# design.net
KiCad netlist of a schematic drawn in EasyEDA Pro
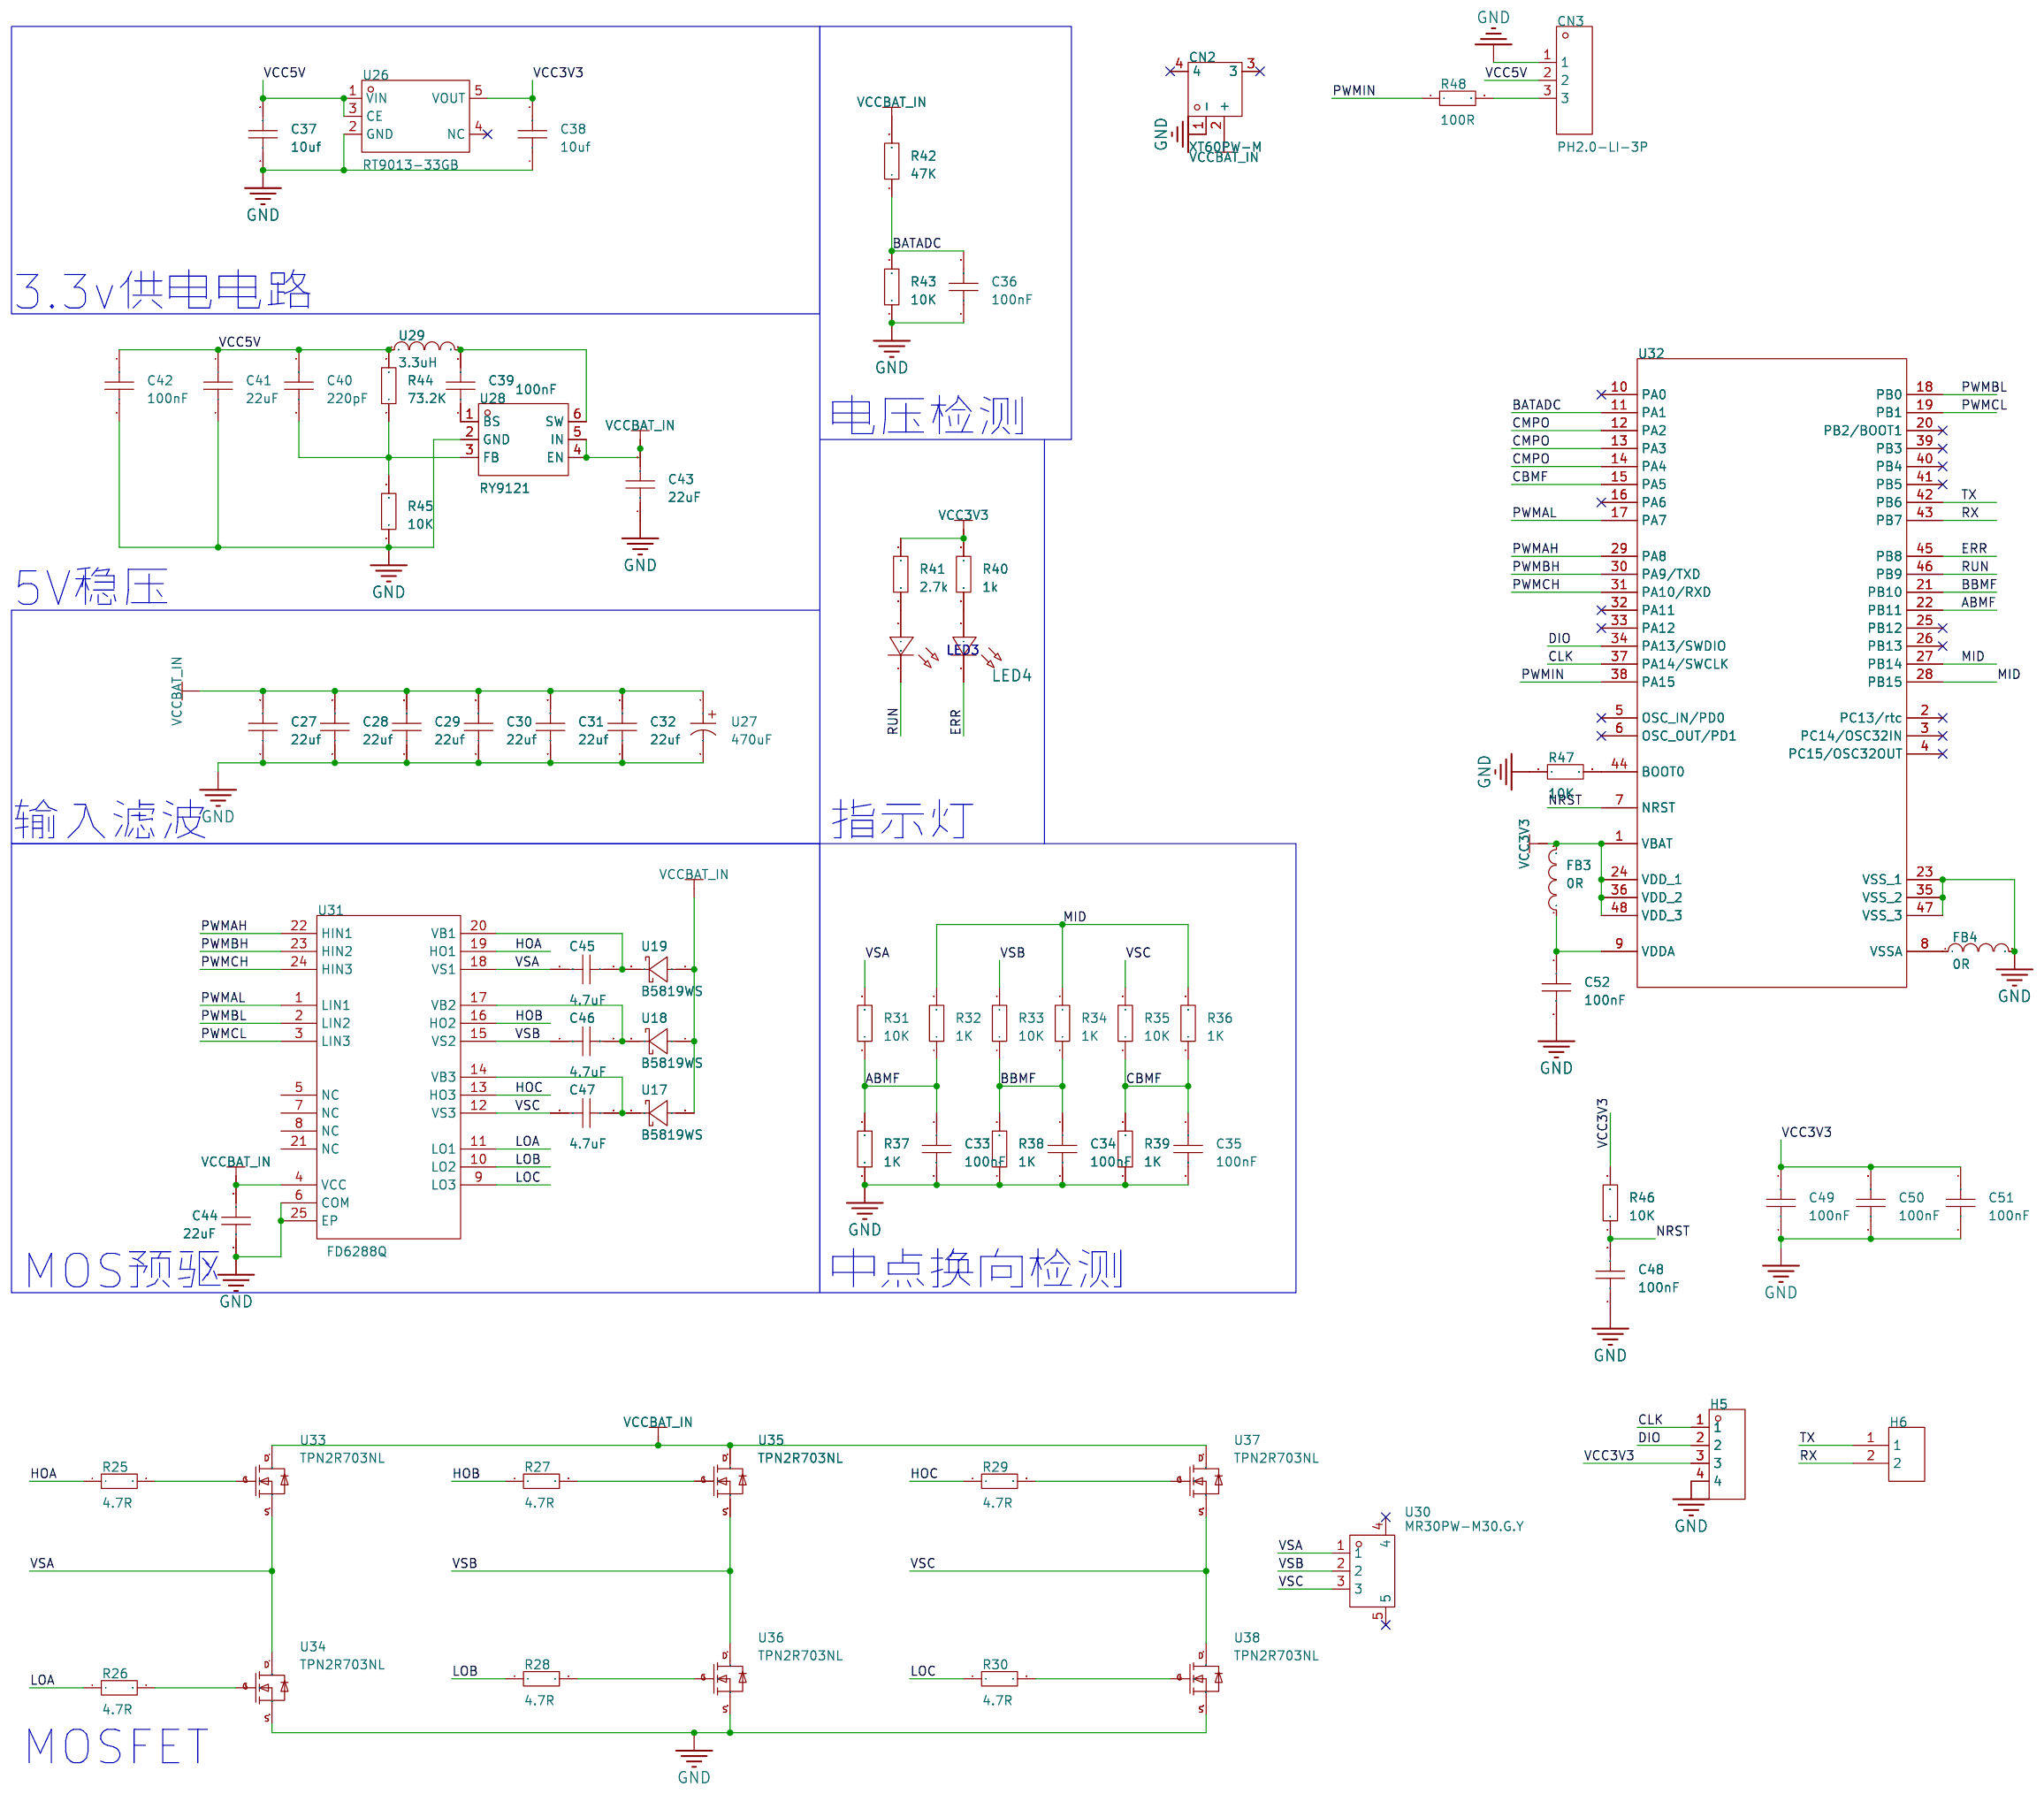
[diagram p0: schematic sheet]

(export (version "E")
  (design (tool "Eeschema 10.0.6"))
  (components
    (comp (ref "C27")
      (value "22uf")
      (footprint "easyedapro:C0603")
      (libsource (lib "easyedapro") (part "CapAcitance"))
    )
    (comp (ref "C28")
      (value "22uf")
      (footprint "easyedapro:C0603")
      (libsource (lib "easyedapro") (part "CapAcitance"))
    )
    (comp (ref "C29")
      (value "22uf")
      (footprint "easyedapro:C0603")
      (libsource (lib "easyedapro") (part "CapAcitance"))
    )
    (comp (ref "C30")
      (value "22uf")
      (footprint "easyedapro:C0603")
      (libsource (lib "easyedapro") (part "CapAcitance"))
    )
    (comp (ref "C31")
      (value "22uf")
      (footprint "easyedapro:C0603")
      (libsource (lib "easyedapro") (part "CapAcitance"))
    )
    (comp (ref "C32")
      (value "22uf")
      (footprint "easyedapro:C0603")
      (libsource (lib "easyedapro") (part "CapAcitance"))
    )
    (comp (ref "C33")
      (value "100nF")
      (footprint "easyedapro:C0603")
      (libsource (lib "easyedapro") (part "CapAcitance"))
    )
    (comp (ref "C34")
      (value "100nF")
      (footprint "easyedapro:C0603")
      (libsource (lib "easyedapro") (part "CapAcitance"))
    )
    (comp (ref "C35")
      (value "100nF")
      (footprint "easyedapro:C0603")
      (libsource (lib "easyedapro") (part "CapAcitance"))
    )
    (comp (ref "C36")
      (value "100nF")
      (footprint "easyedapro:C0603")
      (libsource (lib "easyedapro") (part "CapAcitance"))
    )
    (comp (ref "C37")
      (value "10uf")
      (footprint "easyedapro:C0603")
      (libsource (lib "easyedapro") (part "CapAcitance"))
    )
    (comp (ref "C38")
      (value "10uf")
      (footprint "easyedapro:C0603")
      (libsource (lib "easyedapro") (part "CapAcitance"))
    )
    (comp (ref "C39")
      (value "100nF")
      (footprint "easyedapro:C0603")
      (libsource (lib "easyedapro") (part "CapAcitance"))
    )
    (comp (ref "C40")
      (value "220pF")
      (footprint "easyedapro:C0603")
      (libsource (lib "easyedapro") (part "CapAcitance"))
    )
    (comp (ref "C41")
      (value "22uF")
      (footprint "easyedapro:C0603")
      (libsource (lib "easyedapro") (part "CapAcitance"))
    )
    (comp (ref "C42")
      (value "100nF")
      (footprint "easyedapro:C0603")
      (libsource (lib "easyedapro") (part "CapAcitance"))
    )
    (comp (ref "C43")
      (value "22uF")
      (footprint "easyedapro:C0603")
      (libsource (lib "easyedapro") (part "CapAcitance"))
    )
    (comp (ref "C44")
      (value "22uF")
      (footprint "easyedapro:C0603")
      (libsource (lib "easyedapro") (part "CapAcitance"))
    )
    (comp (ref "C45")
      (value "4.7uF")
      (footprint "easyedapro:C0603")
      (libsource (lib "easyedapro") (part "CapAcitance"))
    )
    (comp (ref "C46")
      (value "4.7uF")
      (footprint "easyedapro:C0603")
      (libsource (lib "easyedapro") (part "CapAcitance"))
    )
    (comp (ref "C47")
      (value "4.7uF")
      (footprint "easyedapro:C0603")
      (libsource (lib "easyedapro") (part "CapAcitance"))
    )
    (comp (ref "C48")
      (value "100nF")
      (footprint "easyedapro:C0603")
      (libsource (lib "easyedapro") (part "CapAcitance"))
    )
    (comp (ref "C49")
      (value "100nF")
      (footprint "easyedapro:C0603")
      (libsource (lib "easyedapro") (part "CapAcitance"))
    )
    (comp (ref "C50")
      (value "100nF")
      (footprint "easyedapro:C0603")
      (libsource (lib "easyedapro") (part "CapAcitance"))
    )
    (comp (ref "C51")
      (value "100nF")
      (footprint "easyedapro:C0603")
      (libsource (lib "easyedapro") (part "CapAcitance"))
    )
    (comp (ref "C52")
      (value "100nF")
      (footprint "easyedapro:C0603")
      (libsource (lib "easyedapro") (part "CapAcitance"))
    )
    (comp (ref "CN2")
      (value "XT60PW-M")
      (footprint "easyedapro:CONN-TH_XT60PW-M")
      (description "模型锂电连接器")
      (fields (field (name "Manufacturer") "AMASS(艾迈斯)"))
      (libsource (lib "easyedapro") (part "XT60PW-M"))
    )
    (comp (ref "CN3")
      (value "PH2.0-LI-3P")
      (footprint "easyedapro:CONN-TH_3P-P2.00_HX20007-3A")
      (libsource (lib "easyedapro") (part "PH2.0-LI-3P"))
    )
    (comp (ref "FB3")
      (value "0R")
      (footprint "easyedapro:L0603")
      (libsource (lib "easyedapro") (part "SDFL1608S100KTF"))
    )
    (comp (ref "FB4")
      (value "0R")
      (footprint "easyedapro:L0603")
      (libsource (lib "easyedapro") (part "SDFL1608S100KTF"))
    )
    (comp (ref "H5") (value "~") (libsource (lib "easyedapro") (part "2.54-1*4p母")))
    (comp (ref "H6")
      (value "~")
      (footprint "easyedapro:HalfHole-2.0-1*2P")
      (libsource (lib "easyedapro") (part "HDR2.0-1*2"))
    )
    (comp (ref "LED3") (value "~") (libsource (lib "easyedapro") (part "led_g")))
    (comp (ref "LED4") (value "~") (libsource (lib "easyedapro") (part "led_r")))
    (comp (ref "R25")
      (value "4.7R")
      (footprint "easyedapro:R0603")
      (libsource (lib "easyedapro") (part "电阻"))
    )
    (comp (ref "R26")
      (value "4.7R")
      (footprint "easyedapro:R0603")
      (libsource (lib "easyedapro") (part "电阻"))
    )
    (comp (ref "R27")
      (value "4.7R")
      (footprint "easyedapro:R0603")
      (libsource (lib "easyedapro") (part "电阻"))
    )
    (comp (ref "R28")
      (value "4.7R")
      (footprint "easyedapro:R0603")
      (libsource (lib "easyedapro") (part "电阻"))
    )
    (comp (ref "R29")
      (value "4.7R")
      (footprint "easyedapro:R0603")
      (libsource (lib "easyedapro") (part "电阻"))
    )
    (comp (ref "R30")
      (value "4.7R")
      (footprint "easyedapro:R0603")
      (libsource (lib "easyedapro") (part "电阻"))
    )
    (comp (ref "R31") (value "10K") (footprint "easyedapro:R0603") (libsource (lib "easyedapro") (part "电阻")))
    (comp (ref "R32") (value "1K") (footprint "easyedapro:R0603") (libsource (lib "easyedapro") (part "电阻")))
    (comp (ref "R33") (value "10K") (footprint "easyedapro:R0603") (libsource (lib "easyedapro") (part "电阻")))
    (comp (ref "R34") (value "1K") (footprint "easyedapro:R0603") (libsource (lib "easyedapro") (part "电阻")))
    (comp (ref "R35") (value "10K") (footprint "easyedapro:R0603") (libsource (lib "easyedapro") (part "电阻")))
    (comp (ref "R36") (value "1K") (footprint "easyedapro:R0603") (libsource (lib "easyedapro") (part "电阻")))
    (comp (ref "R37") (value "1K") (footprint "easyedapro:R0603") (libsource (lib "easyedapro") (part "电阻")))
    (comp (ref "R38") (value "1K") (footprint "easyedapro:R0603") (libsource (lib "easyedapro") (part "电阻")))
    (comp (ref "R39") (value "1K") (footprint "easyedapro:R0603") (libsource (lib "easyedapro") (part "电阻")))
    (comp (ref "R40") (value "1k") (footprint "easyedapro:R0603") (libsource (lib "easyedapro") (part "电阻")))
    (comp (ref "R41")
      (value "2.7k")
      (footprint "easyedapro:R0603")
      (libsource (lib "easyedapro") (part "电阻"))
    )
    (comp (ref "R42") (value "47K") (footprint "easyedapro:R0603") (libsource (lib "easyedapro") (part "电阻")))
    (comp (ref "R43") (value "10K") (footprint "easyedapro:R0603") (libsource (lib "easyedapro") (part "电阻")))
    (comp (ref "R44")
      (value "73.2K")
      (footprint "easyedapro:R0603")
      (libsource (lib "easyedapro") (part "电阻"))
    )
    (comp (ref "R45") (value "10K") (footprint "easyedapro:R0603") (libsource (lib "easyedapro") (part "电阻")))
    (comp (ref "R46") (value "10K") (footprint "easyedapro:R0603") (libsource (lib "easyedapro") (part "电阻")))
    (comp (ref "R47") (value "10K") (footprint "easyedapro:R0603") (libsource (lib "easyedapro") (part "电阻")))
    (comp (ref "R48")
      (value "100R")
      (footprint "easyedapro:R0603")
      (libsource (lib "easyedapro") (part "电阻"))
    )
    (comp (ref "U17")
      (value "B5819WS")
      (footprint "easyedapro:SOD-123_L2.8-W1.8-LS3.7-FD")
      (libsource (lib "easyedapro") (part "B5819WS_C9900015711"))
    )
    (comp (ref "U18")
      (value "B5819WS")
      (footprint "easyedapro:SOD-123_L2.8-W1.8-LS3.7-FD")
      (libsource (lib "easyedapro") (part "B5819WS_C9900015711"))
    )
    (comp (ref "U19")
      (value "B5819WS")
      (footprint "easyedapro:SOD-123_L2.8-W1.8-LS3.7-FD")
      (libsource (lib "easyedapro") (part "B5819WS_C9900015711"))
    )
    (comp (ref "U26")
      (value "RT9013-33GB")
      (footprint "easyedapro:SOT-23-5_L2.9-W1.6-P0.95-LS2.8-BR")
      (fields (field (name "Manufacturer") "TECH PUBLIC(台舟)"))
      (libsource (lib "easyedapro") (part "RT9013-33GB_C19268157"))
    )
    (comp (ref "U27")
      (value "470uF")
      (footprint "easyedapro:CAP-SMD_BD8.0-L8.3-W8.3-LS9.1-FD")
      (description "容值:470uF;精度:±20%;额定电压:16V;纹波电流:390mA@120Hz;等效串联电阻:-;")
      (fields (field (name "Manufacturer Part") "865060353009") (field (name "Manufacturer") "Wurth(伍尔特)"))
      (libsource (lib "easyedapro") (part "865060353009"))
    )
    (comp (ref "U28")
      (value "RY9121")
      (footprint "easyedapro:SOT-23-6_L2.9-W1.6-P0.95-LS2.8-BR")
      (description "功能类型:降压型;输入电压:4.5V~17V;输出电流(最大值):2A;")
      (fields (field (name "Manufacturer") "RYCHiP(蕊源)"))
      (libsource (lib "easyedapro") (part "RY9121"))
    )
    (comp (ref "U29")
      (value "3.3uH")
      (footprint "easyedapro:IND-SMD_L12.3-W12.3_SMDRI127")
      (fields (field (name "Manufacturer Part") "CDRH127R"))
      (libsource (lib "easyedapro") (part "CDRH127R"))
    )
    (comp (ref "U30")
      (value "MR30PW-M30.G.Y")
      (footprint "easyedapro:CONN-TH_MR30PW-M30-G-Y")
      (fields (field (name "Manufacturer") "AMASS(艾迈斯)"))
      (libsource (lib "easyedapro") (part "MR30PW-M30.G.Y"))
    )
    (comp (ref "U31")
      (value "FD6288Q")
      (footprint "easyedapro:QFN-24")
      (libsource (lib "easyedapro") (part "FD6288Q"))
    )
    (comp (ref "U32")
      (value "~")
      (footprint "easyedapro:LQFP-48_L7.0-W7.0-P0.50-LS9.0-BL")
      (libsource (lib "easyedapro") (part "CH32V203C8T6"))
    )
    (comp (ref "U33")
      (value "TPN2R703NL")
      (footprint "easyedapro:TPN2R703NL")
      (libsource (lib "easyedapro") (part "TPN2R703NL"))
    )
    (comp (ref "U34")
      (value "TPN2R703NL")
      (footprint "easyedapro:TPN2R703NL")
      (libsource (lib "easyedapro") (part "TPN2R703NL"))
    )
    (comp (ref "U35")
      (value "TPN2R703NL")
      (footprint "easyedapro:TPN2R703NL")
      (libsource (lib "easyedapro") (part "TPN2R703NL"))
    )
    (comp (ref "U36")
      (value "TPN2R703NL")
      (footprint "easyedapro:TPN2R703NL")
      (libsource (lib "easyedapro") (part "TPN2R703NL"))
    )
    (comp (ref "U37")
      (value "TPN2R703NL")
      (footprint "easyedapro:TPN2R703NL")
      (libsource (lib "easyedapro") (part "TPN2R703NL"))
    )
    (comp (ref "U38")
      (value "TPN2R703NL")
      (footprint "easyedapro:TPN2R703NL")
      (libsource (lib "easyedapro") (part "TPN2R703NL"))
    )
  )
  (nets
    (net (code "1") (name "/ABMF") (class "Default")
      (node (ref "C33") (pin "1") (pinfunction "1_1") (pintype "input"))
      (node (ref "R31") (pin "1") (pinfunction "1_1") (pintype "input"))
      (node (ref "R32") (pin "1") (pinfunction "1_1") (pintype "input"))
      (node (ref "R37") (pin "2") (pinfunction "2_2") (pintype "input"))
      (node (ref "U32") (pin "22") (pinfunction "PB11_22") (pintype "input"))
    )
    (net (code "2") (name "/BATADC") (class "Default")
      (node (ref "C36") (pin "2") (pinfunction "2_2") (pintype "input"))
      (node (ref "R42") (pin "1") (pinfunction "1_1") (pintype "input"))
      (node (ref "R43") (pin "2") (pinfunction "2_2") (pintype "input"))
      (node (ref "U32") (pin "11") (pinfunction "PA1_11") (pintype "input"))
    )
    (net (code "3") (name "/BBMF") (class "Default")
      (node (ref "C34") (pin "1") (pinfunction "1_1") (pintype "input"))
      (node (ref "R33") (pin "1") (pinfunction "1_1") (pintype "input"))
      (node (ref "R34") (pin "1") (pinfunction "1_1") (pintype "input"))
      (node (ref "R38") (pin "2") (pinfunction "2_2") (pintype "input"))
      (node (ref "U32") (pin "21") (pinfunction "PB10_21") (pintype "input"))
    )
    (net (code "4") (name "/CBMF") (class "Default")
      (node (ref "C35") (pin "1") (pinfunction "1_1") (pintype "input"))
      (node (ref "R35") (pin "1") (pinfunction "1_1") (pintype "input"))
      (node (ref "R36") (pin "1") (pinfunction "1_1") (pintype "input"))
      (node (ref "R39") (pin "2") (pinfunction "2_2") (pintype "input"))
      (node (ref "U32") (pin "15") (pinfunction "PA5_15") (pintype "input"))
    )
    (net (code "5") (name "/CLK") (class "Default")
      (node (ref "H5") (pin "1") (pinfunction "1_1") (pintype "input"))
      (node (ref "U32") (pin "37") (pinfunction "PA14/SWCLK_37") (pintype "input"))
    )
    (net (code "6") (name "/CMPO") (class "Default")
      (node (ref "U32") (pin "12") (pinfunction "PA2_12") (pintype "input"))
      (node (ref "U32") (pin "13") (pinfunction "PA3_13") (pintype "input"))
      (node (ref "U32") (pin "14") (pinfunction "PA4_14") (pintype "input"))
    )
    (net (code "7") (name "/DIO") (class "Default")
      (node (ref "H5") (pin "2") (pinfunction "2_2") (pintype "input"))
      (node (ref "U32") (pin "34") (pinfunction "PA13/SWDIO_34") (pintype "input"))
    )
    (net (code "8") (name "/ERR") (class "Default")
      (node (ref "LED4") (pin "1") (pinfunction "C_1") (pintype "input"))
      (node (ref "U32") (pin "45") (pinfunction "PB8_45") (pintype "input"))
    )
    (net (code "9") (name "/HOA") (class "Default")
      (node (ref "R25") (pin "1") (pinfunction "1_1") (pintype "input"))
      (node (ref "U31") (pin "19") (pinfunction "HO1_19") (pintype "output"))
    )
    (net (code "10") (name "/HOB") (class "Default")
      (node (ref "R27") (pin "1") (pinfunction "1_1") (pintype "input"))
      (node (ref "U31") (pin "16") (pinfunction "HO2_16") (pintype "output"))
    )
    (net (code "11") (name "/HOC") (class "Default")
      (node (ref "R29") (pin "1") (pinfunction "1_1") (pintype "input"))
      (node (ref "U31") (pin "13") (pinfunction "HO3_13") (pintype "output"))
    )
    (net (code "12") (name "/LOA") (class "Default")
      (node (ref "R26") (pin "1") (pinfunction "1_1") (pintype "input"))
      (node (ref "U31") (pin "11") (pinfunction "LO1_11") (pintype "output"))
    )
    (net (code "13") (name "/LOB") (class "Default")
      (node (ref "R28") (pin "1") (pinfunction "1_1") (pintype "input"))
      (node (ref "U31") (pin "10") (pinfunction "LO2_10") (pintype "output"))
    )
    (net (code "14") (name "/LOC") (class "Default")
      (node (ref "R30") (pin "1") (pinfunction "1_1") (pintype "input"))
      (node (ref "U31") (pin "9") (pinfunction "LO3_9") (pintype "output"))
    )
    (net (code "15") (name "/MID") (class "Default")
      (node (ref "R32") (pin "2") (pinfunction "2_2") (pintype "input"))
      (node (ref "R34") (pin "2") (pinfunction "2_2") (pintype "input"))
      (node (ref "R36") (pin "2") (pinfunction "2_2") (pintype "input"))
      (node (ref "U32") (pin "27") (pinfunction "PB14_27") (pintype "input"))
      (node (ref "U32") (pin "28") (pinfunction "PB15_28") (pintype "input"))
    )
    (net (code "16") (name "/NRST") (class "Default")
      (node (ref "C48") (pin "2") (pinfunction "2_2") (pintype "input"))
      (node (ref "R46") (pin "1") (pinfunction "1_1") (pintype "input"))
      (node (ref "U32") (pin "7") (pinfunction "NRST_7") (pintype "input"))
    )
    (net (code "17") (name "/PWMAH") (class "Default")
      (node (ref "U31") (pin "22") (pinfunction "HIN1_22") (pintype "input"))
      (node (ref "U32") (pin "29") (pinfunction "PA8_29") (pintype "input"))
    )
    (net (code "18") (name "/PWMAL") (class "Default")
      (node (ref "U31") (pin "1") (pinfunction "LIN1_1") (pintype "input"))
      (node (ref "U32") (pin "17") (pinfunction "PA7_17") (pintype "input"))
    )
    (net (code "19") (name "/PWMBH") (class "Default")
      (node (ref "U31") (pin "23") (pinfunction "HIN2_23") (pintype "input"))
      (node (ref "U32") (pin "30") (pinfunction "PA9/TXD_30") (pintype "input"))
    )
    (net (code "20") (name "/PWMBL") (class "Default")
      (node (ref "U31") (pin "2") (pinfunction "LIN2_2") (pintype "input"))
      (node (ref "U32") (pin "18") (pinfunction "PB0_18") (pintype "input"))
    )
    (net (code "21") (name "/PWMCH") (class "Default")
      (node (ref "U31") (pin "24") (pinfunction "HIN3_24") (pintype "input"))
      (node (ref "U32") (pin "31") (pinfunction "PA10/RXD_31") (pintype "input"))
    )
    (net (code "22") (name "/PWMCL") (class "Default")
      (node (ref "U31") (pin "3") (pinfunction "LIN3_3") (pintype "input"))
      (node (ref "U32") (pin "19") (pinfunction "PB1_19") (pintype "input"))
    )
    (net (code "23") (name "/PWMIN") (class "Default")
      (node (ref "R48") (pin "1") (pinfunction "1_1") (pintype "input"))
      (node (ref "U32") (pin "38") (pinfunction "PA15_38") (pintype "input"))
    )
    (net (code "24") (name "/RUN") (class "Default")
      (node (ref "LED3") (pin "1") (pinfunction "C_1") (pintype "input"))
      (node (ref "U32") (pin "46") (pinfunction "PB9_46") (pintype "input"))
    )
    (net (code "25") (name "/RX") (class "Default")
      (node (ref "H6") (pin "2") (pinfunction "2_2") (pintype "input"))
      (node (ref "U32") (pin "43") (pinfunction "PB7_43") (pintype "input"))
    )
    (net (code "26") (name "/TX") (class "Default")
      (node (ref "H6") (pin "1") (pinfunction "1_1") (pintype "input"))
      (node (ref "U32") (pin "42") (pinfunction "PB6_42") (pintype "input"))
    )
    (net (code "27") (name "/VCC5V") (class "Default")
      (node (ref "C37") (pin "2") (pinfunction "2_2") (pintype "input"))
      (node (ref "C40") (pin "1") (pinfunction "1_1") (pintype "input"))
      (node (ref "C41") (pin "1") (pinfunction "1_1") (pintype "input"))
      (node (ref "C42") (pin "1") (pinfunction "1_1") (pintype "input"))
      (node (ref "CN3") (pin "2") (pinfunction "2_2") (pintype "input"))
      (node (ref "R44") (pin "2") (pinfunction "2_2") (pintype "input"))
      (node (ref "U26") (pin "1") (pinfunction "VIN_1") (pintype "unspecified"))
      (node (ref "U26") (pin "3") (pinfunction "CE_3") (pintype "unspecified"))
      (node (ref "U29") (pin "1") (pinfunction "1_1") (pintype "input"))
    )
    (net (code "28") (name "/VSA") (class "Default")
      (node (ref "C45") (pin "1") (pinfunction "1_1") (pintype "input"))
      (node (ref "R31") (pin "2") (pinfunction "2_2") (pintype "input"))
      (node (ref "U30") (pin "1") (pinfunction "1_1") (pintype "unspecified"))
      (node (ref "U31") (pin "18") (pinfunction "VS1_18") (pintype "input"))
      (node (ref "U33") (pin "3") (pinfunction "S_3") (pintype "unspecified"))
      (node (ref "U34") (pin "1") (pinfunction "D_1") (pintype "unspecified"))
    )
    (net (code "29") (name "/VSB") (class "Default")
      (node (ref "C46") (pin "1") (pinfunction "1_1") (pintype "input"))
      (node (ref "R33") (pin "2") (pinfunction "2_2") (pintype "input"))
      (node (ref "U30") (pin "2") (pinfunction "2_2") (pintype "unspecified"))
      (node (ref "U31") (pin "15") (pinfunction "VS2_15") (pintype "input"))
      (node (ref "U35") (pin "3") (pinfunction "S_3") (pintype "unspecified"))
      (node (ref "U36") (pin "1") (pinfunction "D_1") (pintype "unspecified"))
    )
    (net (code "30") (name "/VSC") (class "Default")
      (node (ref "C47") (pin "1") (pinfunction "1_1") (pintype "input"))
      (node (ref "R35") (pin "2") (pinfunction "2_2") (pintype "input"))
      (node (ref "U30") (pin "3") (pinfunction "3_3") (pintype "unspecified"))
      (node (ref "U31") (pin "12") (pinfunction "VS3_12") (pintype "input"))
      (node (ref "U37") (pin "3") (pinfunction "S_3") (pintype "unspecified"))
      (node (ref "U38") (pin "1") (pinfunction "D_1") (pintype "unspecified"))
    )
    (net (code "31") (name "GND") (class "Default")
      (node (ref "C27") (pin "1") (pinfunction "1_1") (pintype "input"))
      (node (ref "C28") (pin "1") (pinfunction "1_1") (pintype "input"))
      (node (ref "C29") (pin "1") (pinfunction "1_1") (pintype "input"))
      (node (ref "C30") (pin "1") (pinfunction "1_1") (pintype "input"))
      (node (ref "C31") (pin "1") (pinfunction "1_1") (pintype "input"))
      (node (ref "C32") (pin "1") (pinfunction "1_1") (pintype "input"))
      (node (ref "C33") (pin "2") (pinfunction "2_2") (pintype "input"))
      (node (ref "C34") (pin "2") (pinfunction "2_2") (pintype "input"))
      (node (ref "C35") (pin "2") (pinfunction "2_2") (pintype "input"))
      (node (ref "C36") (pin "1") (pinfunction "1_1") (pintype "input"))
      (node (ref "C37") (pin "1") (pinfunction "1_1") (pintype "input"))
      (node (ref "C38") (pin "1") (pinfunction "1_1") (pintype "input"))
      (node (ref "C41") (pin "2") (pinfunction "2_2") (pintype "input"))
      (node (ref "C42") (pin "2") (pinfunction "2_2") (pintype "input"))
      (node (ref "C43") (pin "1") (pinfunction "1_1") (pintype "input"))
      (node (ref "C44") (pin "1") (pinfunction "1_1") (pintype "input"))
      (node (ref "C48") (pin "1") (pinfunction "1_1") (pintype "input"))
      (node (ref "C49") (pin "1") (pinfunction "1_1") (pintype "input"))
      (node (ref "C50") (pin "1") (pinfunction "1_1") (pintype "input"))
      (node (ref "C51") (pin "1") (pinfunction "1_1") (pintype "input"))
      (node (ref "C52") (pin "2") (pinfunction "2_2") (pintype "input"))
      (node (ref "CN2") (pin "1") (pinfunction "-_1") (pintype "input"))
      (node (ref "CN3") (pin "1") (pinfunction "1_1") (pintype "input"))
      (node (ref "FB4") (pin "2") (pinfunction "2_2") (pintype "unspecified"))
      (node (ref "H5") (pin "4") (pinfunction "4_4") (pintype "input"))
      (node (ref "R37") (pin "1") (pinfunction "1_1") (pintype "input"))
      (node (ref "R38") (pin "1") (pinfunction "1_1") (pintype "input"))
      (node (ref "R39") (pin "1") (pinfunction "1_1") (pintype "input"))
      (node (ref "R43") (pin "1") (pinfunction "1_1") (pintype "input"))
      (node (ref "R45") (pin "1") (pinfunction "1_1") (pintype "input"))
      (node (ref "R47") (pin "1") (pinfunction "1_1") (pintype "input"))
      (node (ref "U26") (pin "2") (pinfunction "GND_2") (pintype "unspecified"))
      (node (ref "U27") (pin "2") (pinfunction "2_2") (pintype "input"))
      (node (ref "U28") (pin "2") (pinfunction "GND_2") (pintype "input"))
      (node (ref "U31") (pin "25") (pinfunction "EP_25") (pintype "input"))
      (node (ref "U31") (pin "6") (pinfunction "COM_6") (pintype "input"))
      (node (ref "U32") (pin "23") (pinfunction "VSS_1_23") (pintype "input"))
      (node (ref "U32") (pin "35") (pinfunction "VSS_2_35") (pintype "input"))
      (node (ref "U32") (pin "47") (pinfunction "VSS_3_47") (pintype "input"))
      (node (ref "U34") (pin "3") (pinfunction "S_3") (pintype "unspecified"))
      (node (ref "U36") (pin "3") (pinfunction "S_3") (pintype "unspecified"))
      (node (ref "U38") (pin "3") (pinfunction "S_3") (pintype "unspecified"))
    )
    (net (code "32") (name "Net-(CN3-Pad3)") (class "Default")
      (node (ref "CN3") (pin "3") (pinfunction "3_3") (pintype "input"))
      (node (ref "R48") (pin "2") (pinfunction "2_2") (pintype "input"))
    )
    (net (code "33") (name "Net-(LED3-A)") (class "Default")
      (node (ref "LED3") (pin "2") (pinfunction "A_2") (pintype "input"))
      (node (ref "R41") (pin "2") (pinfunction "2_2") (pintype "input"))
    )
    (net (code "34") (name "Net-(LED4-A)") (class "Default")
      (node (ref "LED4") (pin "2") (pinfunction "A_2") (pintype "input"))
      (node (ref "R40") (pin "2") (pinfunction "2_2") (pintype "input"))
    )
    (net (code "35") (name "Net-(U17-K)") (class "Default")
      (node (ref "C47") (pin "2") (pinfunction "2_2") (pintype "input"))
      (node (ref "U17") (pin "2") (pinfunction "K_2") (pintype "input"))
      (node (ref "U31") (pin "14") (pinfunction "VB3_14") (pintype "input"))
    )
    (net (code "36") (name "Net-(U18-K)") (class "Default")
      (node (ref "C46") (pin "2") (pinfunction "2_2") (pintype "input"))
      (node (ref "U18") (pin "2") (pinfunction "K_2") (pintype "input"))
      (node (ref "U31") (pin "17") (pinfunction "VB2_17") (pintype "input"))
    )
    (net (code "37") (name "Net-(U19-K)") (class "Default")
      (node (ref "C45") (pin "2") (pinfunction "2_2") (pintype "input"))
      (node (ref "U19") (pin "2") (pinfunction "K_2") (pintype "input"))
      (node (ref "U31") (pin "20") (pinfunction "VB1_20") (pintype "input"))
    )
    (net (code "38") (name "Net-(U28-BS)") (class "Default")
      (node (ref "C39") (pin "1") (pinfunction "1_1") (pintype "input"))
      (node (ref "U28") (pin "1") (pinfunction "BS_1") (pintype "input"))
    )
    (net (code "39") (name "Net-(U28-FB)") (class "Default")
      (node (ref "C40") (pin "2") (pinfunction "2_2") (pintype "input"))
      (node (ref "R44") (pin "1") (pinfunction "1_1") (pintype "input"))
      (node (ref "R45") (pin "2") (pinfunction "2_2") (pintype "input"))
      (node (ref "U28") (pin "3") (pinfunction "FB_3") (pintype "input"))
    )
    (net (code "40") (name "Net-(U28-SW)") (class "Default")
      (node (ref "C39") (pin "2") (pinfunction "2_2") (pintype "input"))
      (node (ref "U28") (pin "6") (pinfunction "SW_6") (pintype "input"))
      (node (ref "U29") (pin "2") (pinfunction "2_2") (pintype "input"))
    )
    (net (code "41") (name "Net-(U32-BOOT0)") (class "Default")
      (node (ref "R47") (pin "2") (pinfunction "2_2") (pintype "input"))
      (node (ref "U32") (pin "44") (pinfunction "BOOT0_44") (pintype "input"))
    )
    (net (code "42") (name "Net-(U32-VDDA)") (class "Default")
      (node (ref "C52") (pin "1") (pinfunction "1_1") (pintype "input"))
      (node (ref "FB3") (pin "1") (pinfunction "1_1") (pintype "unspecified"))
      (node (ref "U32") (pin "9") (pinfunction "VDDA_9") (pintype "input"))
    )
    (net (code "43") (name "Net-(U32-VSSA)") (class "Default")
      (node (ref "FB4") (pin "1") (pinfunction "1_1") (pintype "unspecified"))
      (node (ref "U32") (pin "8") (pinfunction "VSSA_8") (pintype "input"))
    )
    (net (code "44") (name "Net-(U33-G)") (class "Default")
      (node (ref "R25") (pin "2") (pinfunction "2_2") (pintype "input"))
      (node (ref "U33") (pin "2") (pinfunction "G_2") (pintype "unspecified"))
    )
    (net (code "45") (name "Net-(U34-G)") (class "Default")
      (node (ref "R26") (pin "2") (pinfunction "2_2") (pintype "input"))
      (node (ref "U34") (pin "2") (pinfunction "G_2") (pintype "unspecified"))
    )
    (net (code "46") (name "Net-(U35-G)") (class "Default")
      (node (ref "R27") (pin "2") (pinfunction "2_2") (pintype "input"))
      (node (ref "U35") (pin "2") (pinfunction "G_2") (pintype "unspecified"))
    )
    (net (code "47") (name "Net-(U36-G)") (class "Default")
      (node (ref "R28") (pin "2") (pinfunction "2_2") (pintype "input"))
      (node (ref "U36") (pin "2") (pinfunction "G_2") (pintype "unspecified"))
    )
    (net (code "48") (name "Net-(U37-G)") (class "Default")
      (node (ref "R29") (pin "2") (pinfunction "2_2") (pintype "input"))
      (node (ref "U37") (pin "2") (pinfunction "G_2") (pintype "unspecified"))
    )
    (net (code "49") (name "Net-(U38-G)") (class "Default")
      (node (ref "R30") (pin "2") (pinfunction "2_2") (pintype "input"))
      (node (ref "U38") (pin "2") (pinfunction "G_2") (pintype "unspecified"))
    )
    (net (code "50") (name "VCC3V3") (class "Default")
      (node (ref "C38") (pin "2") (pinfunction "2_2") (pintype "input"))
      (node (ref "C49") (pin "2") (pinfunction "2_2") (pintype "input"))
      (node (ref "C50") (pin "2") (pinfunction "2_2") (pintype "input"))
      (node (ref "C51") (pin "2") (pinfunction "2_2") (pintype "input"))
      (node (ref "FB3") (pin "2") (pinfunction "2_2") (pintype "unspecified"))
      (node (ref "H5") (pin "3") (pinfunction "3_3") (pintype "input"))
      (node (ref "R40") (pin "1") (pinfunction "1_1") (pintype "input"))
      (node (ref "R41") (pin "1") (pinfunction "1_1") (pintype "input"))
      (node (ref "R46") (pin "2") (pinfunction "2_2") (pintype "input"))
      (node (ref "U26") (pin "5") (pinfunction "VOUT_5") (pintype "unspecified"))
      (node (ref "U32") (pin "1") (pinfunction "VBAT_1") (pintype "input"))
      (node (ref "U32") (pin "24") (pinfunction "VDD_1_24") (pintype "input"))
      (node (ref "U32") (pin "36") (pinfunction "VDD_2_36") (pintype "input"))
      (node (ref "U32") (pin "48") (pinfunction "VDD_3_48") (pintype "input"))
    )
    (net (code "51") (name "VCCBAT_IN") (class "Default")
      (node (ref "C27") (pin "2") (pinfunction "2_2") (pintype "input"))
      (node (ref "C28") (pin "2") (pinfunction "2_2") (pintype "input"))
      (node (ref "C29") (pin "2") (pinfunction "2_2") (pintype "input"))
      (node (ref "C30") (pin "2") (pinfunction "2_2") (pintype "input"))
      (node (ref "C31") (pin "2") (pinfunction "2_2") (pintype "input"))
      (node (ref "C32") (pin "2") (pinfunction "2_2") (pintype "input"))
      (node (ref "C43") (pin "2") (pinfunction "2_2") (pintype "input"))
      (node (ref "C44") (pin "2") (pinfunction "2_2") (pintype "input"))
      (node (ref "CN2") (pin "2") (pinfunction "+_2") (pintype "input"))
      (node (ref "R42") (pin "2") (pinfunction "2_2") (pintype "input"))
      (node (ref "U17") (pin "1") (pinfunction "A_1") (pintype "input"))
      (node (ref "U18") (pin "1") (pinfunction "A_1") (pintype "input"))
      (node (ref "U19") (pin "1") (pinfunction "A_1") (pintype "input"))
      (node (ref "U27") (pin "1") (pinfunction "1_1") (pintype "input"))
      (node (ref "U28") (pin "4") (pinfunction "EN_4") (pintype "input"))
      (node (ref "U28") (pin "5") (pinfunction "IN_5") (pintype "input"))
      (node (ref "U31") (pin "4") (pinfunction "VCC_4") (pintype "input"))
      (node (ref "U33") (pin "1") (pinfunction "D_1") (pintype "unspecified"))
      (node (ref "U35") (pin "1") (pinfunction "D_1") (pintype "unspecified"))
      (node (ref "U37") (pin "1") (pinfunction "D_1") (pintype "unspecified"))
    )
    (net (code "52") (name "unconnected-(CN2-Pad3)") (class "Default")
      (node (ref "CN2") (pin "3") (pinfunction "3_3") (pintype "input+no_connect"))
    )
    (net (code "53") (name "unconnected-(CN2-Pad4)") (class "Default")
      (node (ref "CN2") (pin "4") (pinfunction "4_4") (pintype "input+no_connect"))
    )
    (net (code "54") (name "unconnected-(U26-NC-Pad4)") (class "Default")
      (node (ref "U26") (pin "4") (pinfunction "NC_4") (pintype "unspecified+no_connect"))
    )
    (net (code "55") (name "unconnected-(U30-Pad4)") (class "Default")
      (node (ref "U30") (pin "4") (pinfunction "4_4") (pintype "unspecified+no_connect"))
    )
    (net (code "56") (name "unconnected-(U30-Pad5)") (class "Default")
      (node (ref "U30") (pin "5") (pinfunction "5_5") (pintype "unspecified+no_connect"))
    )
    (net (code "57") (name "unconnected-(U31-NC-Pad5)") (class "Default")
      (node (ref "U31") (pin "5") (pinfunction "NC_5") (pintype "input"))
    )
    (net (code "58") (name "unconnected-(U31-NC-Pad7)") (class "Default")
      (node (ref "U31") (pin "7") (pinfunction "NC_7") (pintype "input"))
    )
    (net (code "59") (name "unconnected-(U31-NC-Pad8)") (class "Default")
      (node (ref "U31") (pin "8") (pinfunction "NC_8") (pintype "input"))
    )
    (net (code "60") (name "unconnected-(U31-NC-Pad21)") (class "Default")
      (node (ref "U31") (pin "21") (pinfunction "NC_21") (pintype "input"))
    )
    (net (code "61") (name "unconnected-(U32-OSC_IN{slash}PD0-Pad5)") (class "Default")
      (node (ref "U32") (pin "5") (pinfunction "OSC_IN/PD0_5") (pintype "input+no_connect"))
    )
    (net (code "62") (name "unconnected-(U32-OSC_OUT{slash}PD1-Pad6)") (class "Default")
      (node (ref "U32") (pin "6") (pinfunction "OSC_OUT/PD1_6") (pintype "input+no_connect"))
    )
    (net (code "63") (name "unconnected-(U32-PA0-Pad10)") (class "Default")
      (node (ref "U32") (pin "10") (pinfunction "PA0_10") (pintype "input+no_connect"))
    )
    (net (code "64") (name "unconnected-(U32-PA6-Pad16)") (class "Default")
      (node (ref "U32") (pin "16") (pinfunction "PA6_16") (pintype "input+no_connect"))
    )
    (net (code "65") (name "unconnected-(U32-PA11-Pad32)") (class "Default")
      (node (ref "U32") (pin "32") (pinfunction "PA11_32") (pintype "input+no_connect"))
    )
    (net (code "66") (name "unconnected-(U32-PA12-Pad33)") (class "Default")
      (node (ref "U32") (pin "33") (pinfunction "PA12_33") (pintype "input+no_connect"))
    )
    (net (code "67") (name "unconnected-(U32-PB2{slash}BOOT1-Pad20)") (class "Default")
      (node (ref "U32") (pin "20") (pinfunction "PB2/BOOT1_20") (pintype "input+no_connect"))
    )
    (net (code "68") (name "unconnected-(U32-PB3-Pad39)") (class "Default")
      (node (ref "U32") (pin "39") (pinfunction "PB3_39") (pintype "input+no_connect"))
    )
    (net (code "69") (name "unconnected-(U32-PB4-Pad40)") (class "Default")
      (node (ref "U32") (pin "40") (pinfunction "PB4_40") (pintype "input+no_connect"))
    )
    (net (code "70") (name "unconnected-(U32-PB5-Pad41)") (class "Default")
      (node (ref "U32") (pin "41") (pinfunction "PB5_41") (pintype "input+no_connect"))
    )
    (net (code "71") (name "unconnected-(U32-PB12-Pad25)") (class "Default")
      (node (ref "U32") (pin "25") (pinfunction "PB12_25") (pintype "input+no_connect"))
    )
    (net (code "72") (name "unconnected-(U32-PB13-Pad26)") (class "Default")
      (node (ref "U32") (pin "26") (pinfunction "PB13_26") (pintype "input+no_connect"))
    )
    (net (code "73") (name "unconnected-(U32-PC13{slash}rtc-Pad2)") (class "Default")
      (node (ref "U32") (pin "2") (pinfunction "PC13/rtc_2") (pintype "input+no_connect"))
    )
    (net (code "74") (name "unconnected-(U32-PC14{slash}OSC32IN-Pad3)") (class "Default")
      (node (ref "U32") (pin "3") (pinfunction "PC14/OSC32IN_3") (pintype "input+no_connect"))
    )
    (net (code "75") (name "unconnected-(U32-PC15{slash}OSC32OUT-Pad4)") (class "Default")
      (node (ref "U32") (pin "4") (pinfunction "PC15/OSC32OUT_4") (pintype "input+no_connect"))
    )
  )
)
